# RELAY15.net
KiCad netlist of a schematic drawn in Altium Designer
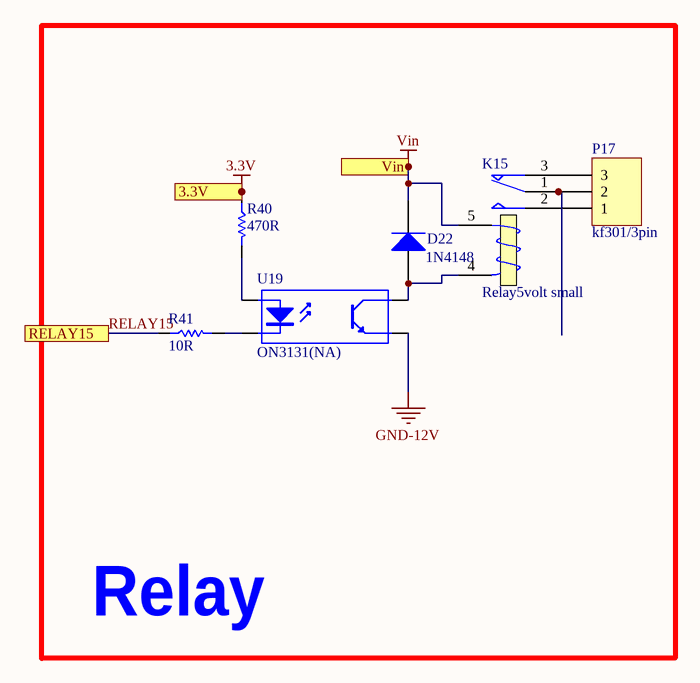
[diagram p0: RELAY15.SchDoc]

(export (version "E")
  (design (tool "Eeschema 10.0.6"))
  (components
    (comp (ref "D22")
      (value "1N4148")
      (footprint "sod123")
      (description "1 Amp General Purpose Rectifier")
      (fields (field (name "PUBLISHER") "Altium Limited"))
      (libsource (lib "Miscellaneous Devices") (part "Diode 1N4007"))
    )
    (comp (ref "K15")
      (value "Relay5volt small")
      (footprint "relay5_childern")
      (description "SPDT Relay")
      (fields (field (name "PUBLISHER") "Altium Limited"))
      (libsource (lib "FLIB") (part "Relay"))
    )
    (comp (ref "P17")
      (value "kf301/3pin")
      (footprint "Blue Connector 1*3 -kf301")
      (fields (field (name "PUBLISHER") "Altium Limited"))
      (libsource (lib "Miscellaneous Connectors") (part "Header 3"))
    )
    (comp (ref "R40")
      (value "470R")
      (footprint "0805/resistor")
      (description "Resistor")
      (fields (field (name "TOLERANCE") "5%") (field (name "POWER") "1/8 W"))
      (libsource (lib "skille") (part "Resistor"))
    )
    (comp (ref "R41")
      (value "10R")
      (footprint "0805/resistor")
      (description "Resistor")
      (fields (field (name "TOLERANCE") "5%") (field (name "POWER") "1/8 W"))
      (libsource (lib "skille") (part "Resistor"))
    )
    (comp (ref "U19")
      (value "ON3131(NA)")
      (footprint "OPTO_COUPLER")
      (description "4-Pin Phototransistor Optocoupler")
      (fields (field (name "PUBLISHER") "Altium Limited"))
      (libsource (lib "skille") (part "Optoisolator1"))
    )
  )
  (nets
    (net (code "1") (name "/RELAY15") (class "Default")
      (node (ref "R41") (pin "1") (pinfunction "1_1") (pintype "passive"))
    )
    (net (code "2") (name "3.3V") (class "Default")
      (node (ref "R40") (pin "1") (pinfunction "1_1") (pintype "passive"))
    )
    (net (code "3") (name "GND-12V") (class "Default")
      (node (ref "U19") (pin "3") (pinfunction "E_3") (pintype "passive"))
    )
    (net (code "4") (name "Net-(K15-COM)") (class "Default")
      (node (ref "K15") (pin "1") (pinfunction "COM_1") (pintype "passive"))
      (node (ref "P17") (pin "2") (pinfunction "2_2") (pintype "passive"))
    )
    (net (code "5") (name "Net-(K15-NO)") (class "Default")
      (node (ref "K15") (pin "2") (pinfunction "NO_2") (pintype "passive"))
      (node (ref "P17") (pin "1") (pinfunction "1_1") (pintype "passive"))
    )
    (net (code "6") (name "Net-(K15-T1)") (class "Default")
      (node (ref "K15") (pin "3") (pinfunction "T1_3") (pintype "passive"))
      (node (ref "P17") (pin "3") (pinfunction "3_3") (pintype "passive"))
    )
    (net (code "7") (name "Net-(K15-T2)") (class "Default")
      (node (ref "D22") (pin "A") (pinfunction "A_A") (pintype "passive"))
      (node (ref "K15") (pin "4") (pinfunction "T2_4") (pintype "passive"))
      (node (ref "U19") (pin "4") (pinfunction "C_4") (pintype "passive"))
    )
    (net (code "8") (name "Net-(U19-A)") (class "Default")
      (node (ref "R40") (pin "2") (pinfunction "2_2") (pintype "passive"))
      (node (ref "U19") (pin "1") (pinfunction "A_1") (pintype "passive"))
    )
    (net (code "9") (name "Net-(U19-K)") (class "Default")
      (node (ref "R41") (pin "2") (pinfunction "2_2") (pintype "passive"))
      (node (ref "U19") (pin "2") (pinfunction "K_2") (pintype "passive"))
    )
    (net (code "10") (name "Vin") (class "Default")
      (node (ref "D22") (pin "K") (pinfunction "K_K") (pintype "passive"))
      (node (ref "K15") (pin "5") (pinfunction "5_5") (pintype "passive"))
    )
  )
)
